# Thermistors.net
KiCad netlist of a schematic drawn in Altium Designer
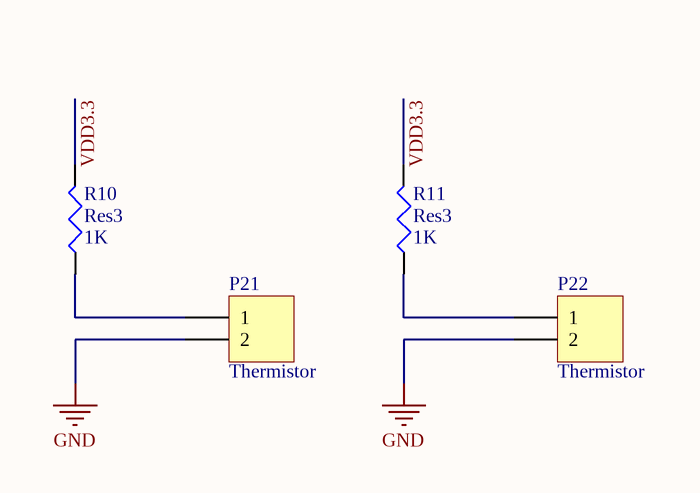
[diagram p0: Thermistors.SchDoc]

(export (version "E")
  (design (tool "Eeschema 10.0.6"))
  (components
    (comp (ref "P21")
      (value "Thermistor")
      (footprint "HDR1X2")
      (description "Header, 2-Pin")
      (fields (field (name "PUBLISHER") "Altium Limited"))
      (libsource (lib "Miscellaneous Connectors") (part "Header 2"))
    )
    (comp (ref "P22")
      (value "Thermistor")
      (footprint "HDR1X2")
      (description "Header, 2-Pin")
      (fields (field (name "PUBLISHER") "Altium Limited"))
      (libsource (lib "Miscellaneous Connectors") (part "Header 2"))
    )
    (comp (ref "R10")
      (value "Res3")
      (footprint "6-0805_L")
      (description "Resistor")
      (fields (field (name "ALTIUM_VALUE") "1K") (field (name "PUBLISHER") "Altium Limited"))
      (libsource (lib "Miscellaneous Devices") (part "Res3"))
    )
    (comp (ref "R11")
      (value "Res3")
      (footprint "6-0805_L")
      (description "Resistor")
      (fields (field (name "ALTIUM_VALUE") "1K") (field (name "PUBLISHER") "Altium Limited"))
      (libsource (lib "Miscellaneous Devices") (part "Res3"))
    )
  )
  (nets
    (net (code "1") (name "/VDD3.3") (class "Default")
      (node (ref "R10") (pin "2") (pinfunction "2_2") (pintype "passive"))
      (node (ref "R11") (pin "2") (pinfunction "2_2") (pintype "passive"))
    )
    (net (code "2") (name "GND") (class "Default")
      (node (ref "P21") (pin "2") (pinfunction "2_2") (pintype "passive"))
      (node (ref "P22") (pin "2") (pinfunction "2_2") (pintype "passive"))
    )
    (net (code "3") (name "Net-(P21-Pad1)") (class "Default")
      (node (ref "P21") (pin "1") (pinfunction "1_1") (pintype "passive"))
      (node (ref "R10") (pin "1") (pinfunction "1_1") (pintype "passive"))
    )
    (net (code "4") (name "Net-(P22-Pad1)") (class "Default")
      (node (ref "P22") (pin "1") (pinfunction "1_1") (pintype "passive"))
      (node (ref "R11") (pin "1") (pinfunction "1_1") (pintype "passive"))
    )
  )
)
